# 03_MCU.net
KiCad netlist of a schematic drawn in Altium Designer
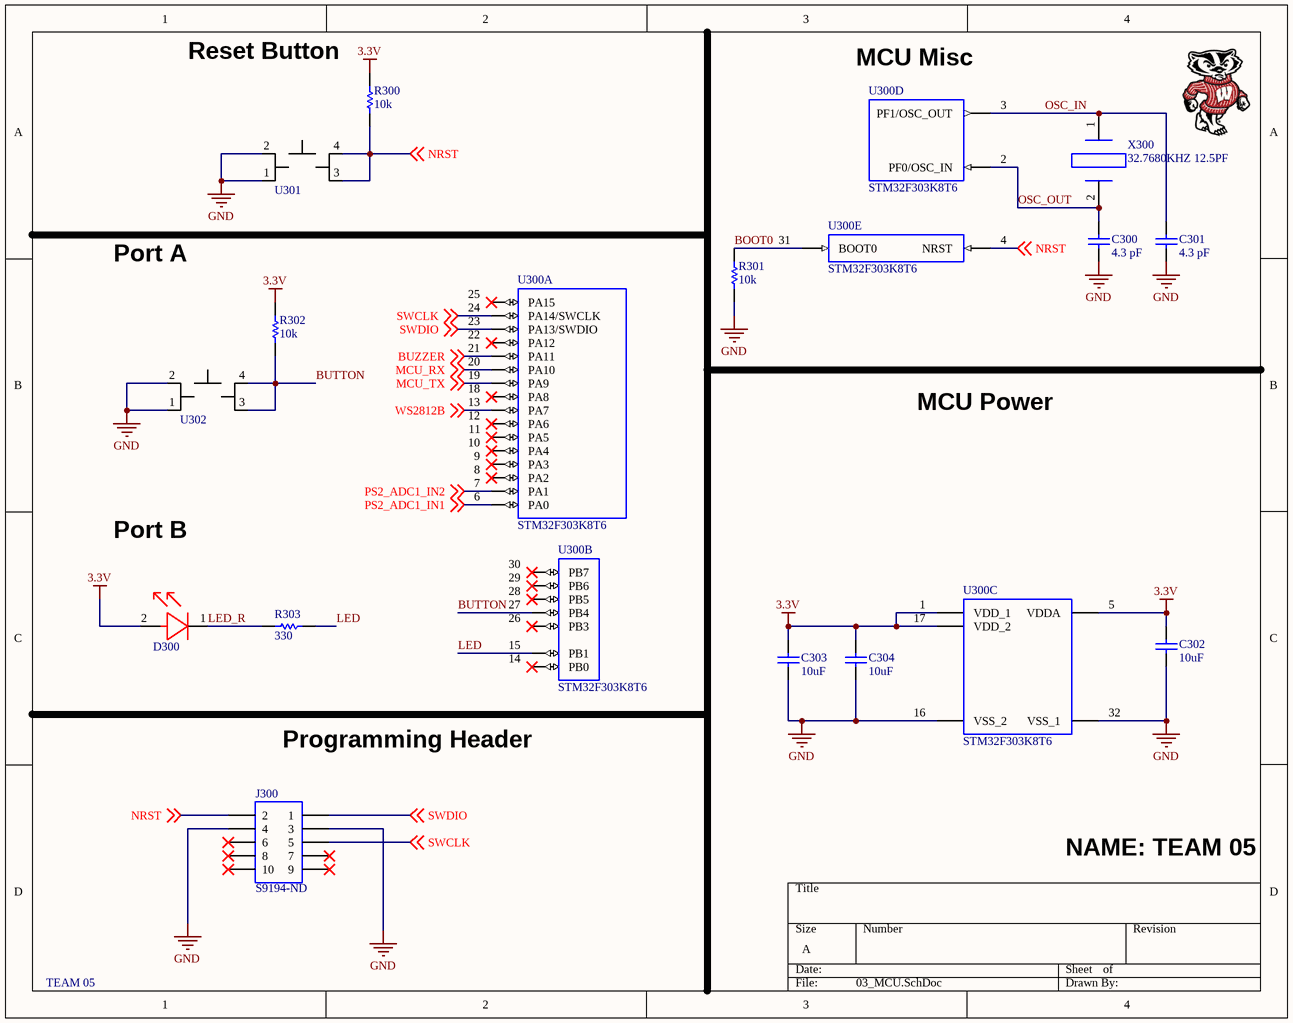
[diagram p0: 03_MCU.SchDoc]

(export (version "E")
  (design (tool "Eeschema 10.0.6"))
  (components
    (comp (ref "C300")
      (value "CAP_0805_P_004.30")
      (footprint "CAP_0805")
      (description "CAP CER 4.3PF 100V NP0 0805")
      (fields
        (field (name "MANUFACTURER") "Kyocera AVX")
        (field (name "MANUFACTURER PART NUMBER") "08051A4R3CAT2A")
        (field (name "CAPACITANCE VALUE") "4.3 pF")
      )
      (libsource (lib "ece315-S20") (part "CAP_0805_P_004.30"))
    )
    (comp (ref "C301")
      (value "CAP_0805_P_004.30")
      (footprint "CAP_0805")
      (description "CAP CER 4.3PF 100V NP0 0805")
      (fields
        (field (name "MANUFACTURER") "Kyocera AVX")
        (field (name "MANUFACTURER PART NUMBER") "08051A4R3CAT2A")
        (field (name "CAPACITANCE VALUE") "4.3 pF")
      )
      (libsource (lib "ece315-S20") (part "CAP_0805_P_004.30"))
    )
    (comp (ref "C302")
      (value "10uF")
      (footprint "CAP_0805")
      (description "CAP CER 10UF 16V X7R 0805")
      (fields
        (field (name "MANUFACTURER") "Samsung")
        (field (name "MANUFACTURER PART NUMBER") "CL21A106KPCLQNC")
        (field (name "CAPACITANCE") "10uF")
      )
      (libsource (lib "ece315-S20") (part "CAP_0805_U_010.00"))
    )
    (comp (ref "C303")
      (value "10uF")
      (footprint "CAP_0805")
      (description "CAP CER 10UF 16V X7R 0805")
      (fields
        (field (name "MANUFACTURER") "Samsung")
        (field (name "MANUFACTURER PART NUMBER") "CL21A106KPCLQNC")
        (field (name "CAPACITANCE") "10uF")
      )
      (libsource (lib "ece315-S20") (part "CAP_0805_U_010.00"))
    )
    (comp (ref "C304")
      (value "10uF")
      (footprint "CAP_0805")
      (description "CAP CER 10UF 16V X7R 0805")
      (fields
        (field (name "MANUFACTURER") "Samsung")
        (field (name "MANUFACTURER PART NUMBER") "CL21A106KPCLQNC")
        (field (name "CAPACITANCE") "10uF")
      )
      (libsource (lib "ece315-S20") (part "CAP_0805_U_010.00"))
    )
    (comp (ref "D300")
      (value "LED_RED_0805.1")
      (footprint "LED_RED_0805")
      (description "LED SUPER RED CLR THIN 0805 SMD")
      (fields
        (field (name "MANUFACTURER") "Vishay / Lite-On")
        (field (name "MANUFACTURER PART NUMBER") "LTST-C171KRKT")
      )
      (libsource (lib "ece315-S20") (part "LED_RED_0805.1"))
    )
    (comp (ref "J300")
      (value "SFH11-PBPC-D05-ST-BK")
      (footprint "SFH11-PBPC-D05-ST-BK")
      (description "CONN HDR 10POS 0.1 GOLD PCB")
      (fields (field (name "SUPPLIER PART NUMBER 1") "S9194-ND"))
      (libsource (lib "ece315-S20") (part "SFH11-PBPC-D05-ST-BK"))
    )
    (comp (ref "R300")
      (value "10K")
      (footprint "RES_0805")
      (description "RES SMD 10K OHM 1% 1/8W 0805")
      (fields
        (field (name "MANUFACTURER") "Panasonic / Panasonic ECG")
        (field (name "MANUFACTURER PART NUMBER") "ERJ-6ENF1002V")
        (field (name "RESISTANCE") "10k")
      )
      (libsource (lib "ece315-S20") (part "RES_0805_K_010.00"))
    )
    (comp (ref "R301")
      (value "10K")
      (footprint "RES_0805")
      (description "RES SMD 10K OHM 1% 1/8W 0805")
      (fields
        (field (name "MANUFACTURER") "Panasonic / Panasonic ECG")
        (field (name "MANUFACTURER PART NUMBER") "ERJ-6ENF1002V")
        (field (name "RESISTANCE") "10k")
      )
      (libsource (lib "ece315-S20") (part "RES_0805_K_010.00"))
    )
    (comp (ref "R302")
      (value "10K")
      (footprint "RES_0805")
      (description "RES SMD 10K OHM 1% 1/8W 0805")
      (fields
        (field (name "MANUFACTURER") "Panasonic / Panasonic ECG")
        (field (name "MANUFACTURER PART NUMBER") "ERJ-6ENF1002V")
        (field (name "RESISTANCE") "10k")
      )
      (libsource (lib "ece315-S20") (part "RES_0805_K_010.00"))
    )
    (comp (ref "R303")
      (value "330")
      (footprint "RES_0805")
      (description "RES SMD 330 OHM 1% 1/8W 0805")
      (fields
        (field (name "MANUFACTURER") "Panasonic / Panasonic ECG")
        (field (name "MANUFACTURER PART NUMBER") "ERJ-6ENF3300V")
        (field (name "RESISTANCE") "330")
      )
      (libsource (lib "ece315-S20") (part "RES_0805_R_330.00"))
    )
    (comp (ref "U300")
      (value "IC_STM32F303K8T6")
      (footprint "LQFP32")
      (description "ARM® Cortex®-M4 STM32 F3 Microcontroller IC 32-Bit 72MHz 64KB (64K x 8) FLASH 32-LQFP (7x7)")
      (fields
        (field (name "MANUFACTURER") "STMicroelectronics")
        (field (name "MANUFACTURER PART NUMBER") "STM32F303K8T6")
      )
      (libsource (lib "ece315-S20") (part "IC_STM32F303K8T6"))
    )
    (comp (ref "U301")
      (value "SWITCH_6mm_6mm_smd")
      (footprint "SWITCH_6mm_6mm_smd")
      (description "SWITCH TACTILE SPST-NO 0.05A 12V")
      (fields
        (field (name "MANUFACTURER") "C&K Components")
        (field (name "MANUFACTURER PART NUMBER") "PTS645SH50SMTR92 LFS")
      )
      (libsource (lib "ece315-S20") (part "SWITCH_6mm_6mm_smd"))
    )
    (comp (ref "U302")
      (value "SWITCH_6mm_6mm_smd")
      (footprint "SWITCH_6mm_6mm_smd")
      (description "SWITCH TACTILE SPST-NO 0.05A 12V")
      (fields
        (field (name "MANUFACTURER") "C&K Components")
        (field (name "MANUFACTURER PART NUMBER") "PTS645SH50SMTR92 LFS")
      )
      (libsource (lib "ece315-S20") (part "SWITCH_6mm_6mm_smd"))
    )
    (comp (ref "X300")
      (value "32.7680KHZ 12.5PF")
      (footprint "NX3215SA-32.768K-STD-MUA-8")
      (description "CRYSTAL 32.768KHZ 12.5PF SMD")
      (fields
        (field (name "MANUFACTURER") "Nihon Dempa Kogyo (NDK)")
        (field (name "MANUFACTURER PART NUMBER") "NX3215SA-32.768K-STD-MUA-8")
      )
      (libsource (lib "ece315-S20") (part "CRYSTAL_NX3215SA-32.768K"))
    )
  )
  (nets
    (net (code "1") (name "/BOOT0") (class "Default")
      (node (ref "R301") (pin "2") (pinfunction "2_2") (pintype "passive"))
      (node (ref "U300") (pin "31") (pinfunction "BOOT0_31") (pintype "input"))
    )
    (net (code "2") (name "/BUTTON") (class "Default")
      (node (ref "R302") (pin "1") (pinfunction "1_1") (pintype "passive"))
      (node (ref "U300") (pin "27") (pinfunction "PB4_27") (pintype "bidirectional"))
      (node (ref "U302") (pin "3") (pinfunction "3_3") (pintype "passive"))
      (node (ref "U302") (pin "4") (pinfunction "VCCIO_4") (pintype "passive"))
    )
    (net (code "3") (name "/LED") (class "Default")
      (node (ref "R303") (pin "2") (pinfunction "2_2") (pintype "passive"))
      (node (ref "U300") (pin "15") (pinfunction "PB1_15") (pintype "bidirectional"))
    )
    (net (code "4") (name "/LED_R") (class "Default")
      (node (ref "D300") (pin "1") (pinfunction "Cathode_1") (pintype "passive"))
      (node (ref "R303") (pin "1") (pinfunction "1_1") (pintype "passive"))
    )
    (net (code "5") (name "/OSC_IN") (class "Default")
      (node (ref "C301") (pin "2") (pinfunction "2_2") (pintype "passive"))
      (node (ref "U300") (pin "3") (pinfunction "PF1/OSC_OUT_3") (pintype "output"))
      (node (ref "X300") (pin "1") (pinfunction "1_1") (pintype "passive"))
    )
    (net (code "6") (name "/OSC_OUT") (class "Default")
      (node (ref "C300") (pin "2") (pinfunction "2_2") (pintype "passive"))
      (node (ref "U300") (pin "2") (pinfunction "PF0/OSC_IN_2") (pintype "input"))
      (node (ref "X300") (pin "2") (pinfunction "2_2") (pintype "passive"))
    )
    (net (code "7") (name "3.3V") (class "Default")
      (node (ref "C302") (pin "2") (pinfunction "2_2") (pintype "passive"))
      (node (ref "C303") (pin "2") (pinfunction "2_2") (pintype "passive"))
      (node (ref "C304") (pin "2") (pinfunction "2_2") (pintype "passive"))
      (node (ref "D300") (pin "2") (pinfunction "Anode_2") (pintype "passive"))
      (node (ref "R300") (pin "2") (pinfunction "2_2") (pintype "passive"))
      (node (ref "R302") (pin "2") (pinfunction "2_2") (pintype "passive"))
      (node (ref "U300") (pin "1") (pinfunction "VDD_1_1") (pintype "power_in"))
      (node (ref "U300") (pin "17") (pinfunction "VDD_2_17") (pintype "power_in"))
      (node (ref "U300") (pin "5") (pinfunction "VDDA_5") (pintype "power_in"))
    )
    (net (code "8") (name "BUZZER") (class "Default")
      (node (ref "U300") (pin "21") (pinfunction "PA11_21") (pintype "bidirectional"))
    )
    (net (code "9") (name "GND") (class "Default")
      (node (ref "C300") (pin "1") (pinfunction "1_1") (pintype "passive"))
      (node (ref "C301") (pin "1") (pinfunction "1_1") (pintype "passive"))
      (node (ref "C302") (pin "1") (pinfunction "1_1") (pintype "passive"))
      (node (ref "C303") (pin "1") (pinfunction "1_1") (pintype "passive"))
      (node (ref "C304") (pin "1") (pinfunction "1_1") (pintype "passive"))
      (node (ref "J300") (pin "3") (pinfunction "3_3") (pintype "passive"))
      (node (ref "J300") (pin "4") (pinfunction "4_4") (pintype "passive"))
      (node (ref "R301") (pin "1") (pinfunction "1_1") (pintype "passive"))
      (node (ref "U300") (pin "16") (pinfunction "VSS_2_16") (pintype "power_in"))
      (node (ref "U300") (pin "32") (pinfunction "VSS_1_32") (pintype "power_in"))
      (node (ref "U301") (pin "1") (pinfunction "1_1") (pintype "passive"))
      (node (ref "U301") (pin "2") (pinfunction "2_2") (pintype "passive"))
      (node (ref "U302") (pin "1") (pinfunction "1_1") (pintype "passive"))
      (node (ref "U302") (pin "2") (pinfunction "2_2") (pintype "passive"))
    )
    (net (code "10") (name "MCU_RX") (class "Default")
      (node (ref "U300") (pin "20") (pinfunction "PA10_20") (pintype "bidirectional"))
    )
    (net (code "11") (name "MCU_TX") (class "Default")
      (node (ref "U300") (pin "19") (pinfunction "PA9_19") (pintype "bidirectional"))
    )
    (net (code "12") (name "NRST") (class "Default")
      (node (ref "J300") (pin "2") (pinfunction "2_2") (pintype "passive"))
      (node (ref "R300") (pin "1") (pinfunction "1_1") (pintype "passive"))
      (node (ref "U300") (pin "4") (pinfunction "NRST_4") (pintype "input"))
      (node (ref "U301") (pin "3") (pinfunction "3_3") (pintype "passive"))
      (node (ref "U301") (pin "4") (pinfunction "VCCIO_4") (pintype "passive"))
    )
    (net (code "13") (name "PS2_ADC1_IN1") (class "Default")
      (node (ref "U300") (pin "6") (pinfunction "PA0_6") (pintype "bidirectional"))
    )
    (net (code "14") (name "PS2_ADC1_IN2") (class "Default")
      (node (ref "U300") (pin "7") (pinfunction "PA1_7") (pintype "bidirectional"))
    )
    (net (code "15") (name "SWCLK") (class "Default")
      (node (ref "J300") (pin "5") (pinfunction "5_5") (pintype "passive"))
      (node (ref "U300") (pin "24") (pinfunction "PA14/SWCLK_24") (pintype "bidirectional"))
    )
    (net (code "16") (name "SWDIO") (class "Default")
      (node (ref "J300") (pin "1") (pinfunction "1_1") (pintype "passive"))
      (node (ref "U300") (pin "23") (pinfunction "PA13/SWDIO_23") (pintype "bidirectional"))
    )
    (net (code "17") (name "WS2812B") (class "Default")
      (node (ref "U300") (pin "13") (pinfunction "PA7_13") (pintype "bidirectional"))
    )
    (net (code "18") (name "unconnected-(J300-Pad6)") (class "Default")
      (node (ref "J300") (pin "6") (pinfunction "6_6") (pintype "passive+no_connect"))
    )
    (net (code "19") (name "unconnected-(J300-Pad7)") (class "Default")
      (node (ref "J300") (pin "7") (pinfunction "7_7") (pintype "passive+no_connect"))
    )
    (net (code "20") (name "unconnected-(J300-Pad8)") (class "Default")
      (node (ref "J300") (pin "8") (pinfunction "8_8") (pintype "passive+no_connect"))
    )
    (net (code "21") (name "unconnected-(J300-Pad9)") (class "Default")
      (node (ref "J300") (pin "9") (pinfunction "9_9") (pintype "passive+no_connect"))
    )
    (net (code "22") (name "unconnected-(J300-Pad10)") (class "Default")
      (node (ref "J300") (pin "10") (pinfunction "10_10") (pintype "passive+no_connect"))
    )
    (net (code "23") (name "unconnected-(U300A-PA2-Pad8)") (class "Default")
      (node (ref "U300") (pin "8") (pinfunction "PA2_8") (pintype "bidirectional+no_connect"))
    )
    (net (code "24") (name "unconnected-(U300A-PA3-Pad9)") (class "Default")
      (node (ref "U300") (pin "9") (pinfunction "PA3_9") (pintype "bidirectional+no_connect"))
    )
    (net (code "25") (name "unconnected-(U300A-PA4-Pad10)") (class "Default")
      (node (ref "U300") (pin "10") (pinfunction "PA4_10") (pintype "bidirectional+no_connect"))
    )
    (net (code "26") (name "unconnected-(U300A-PA5-Pad11)") (class "Default")
      (node (ref "U300") (pin "11") (pinfunction "PA5_11") (pintype "bidirectional+no_connect"))
    )
    (net (code "27") (name "unconnected-(U300A-PA6-Pad12)") (class "Default")
      (node (ref "U300") (pin "12") (pinfunction "PA6_12") (pintype "bidirectional+no_connect"))
    )
    (net (code "28") (name "unconnected-(U300A-PA8-Pad18)") (class "Default")
      (node (ref "U300") (pin "18") (pinfunction "PA8_18") (pintype "bidirectional+no_connect"))
    )
    (net (code "29") (name "unconnected-(U300A-PA12-Pad22)") (class "Default")
      (node (ref "U300") (pin "22") (pinfunction "PA12_22") (pintype "bidirectional+no_connect"))
    )
    (net (code "30") (name "unconnected-(U300A-PA15-Pad25)") (class "Default")
      (node (ref "U300") (pin "25") (pinfunction "PA15_25") (pintype "bidirectional+no_connect"))
    )
    (net (code "31") (name "unconnected-(U300B-PB0-Pad14)") (class "Default")
      (node (ref "U300") (pin "14") (pinfunction "PB0_14") (pintype "bidirectional+no_connect"))
    )
    (net (code "32") (name "unconnected-(U300B-PB3-Pad26)") (class "Default")
      (node (ref "U300") (pin "26") (pinfunction "PB3_26") (pintype "bidirectional+no_connect"))
    )
    (net (code "33") (name "unconnected-(U300B-PB5-Pad28)") (class "Default")
      (node (ref "U300") (pin "28") (pinfunction "PB5_28") (pintype "bidirectional+no_connect"))
    )
    (net (code "34") (name "unconnected-(U300B-PB6-Pad29)") (class "Default")
      (node (ref "U300") (pin "29") (pinfunction "PB6_29") (pintype "bidirectional+no_connect"))
    )
    (net (code "35") (name "unconnected-(U300B-PB7-Pad30)") (class "Default")
      (node (ref "U300") (pin "30") (pinfunction "PB7_30") (pintype "bidirectional+no_connect"))
    )
  )
)
